# outputs-voltage-and-current-measurements.net
KiCad netlist of a schematic drawn in Altium Designer
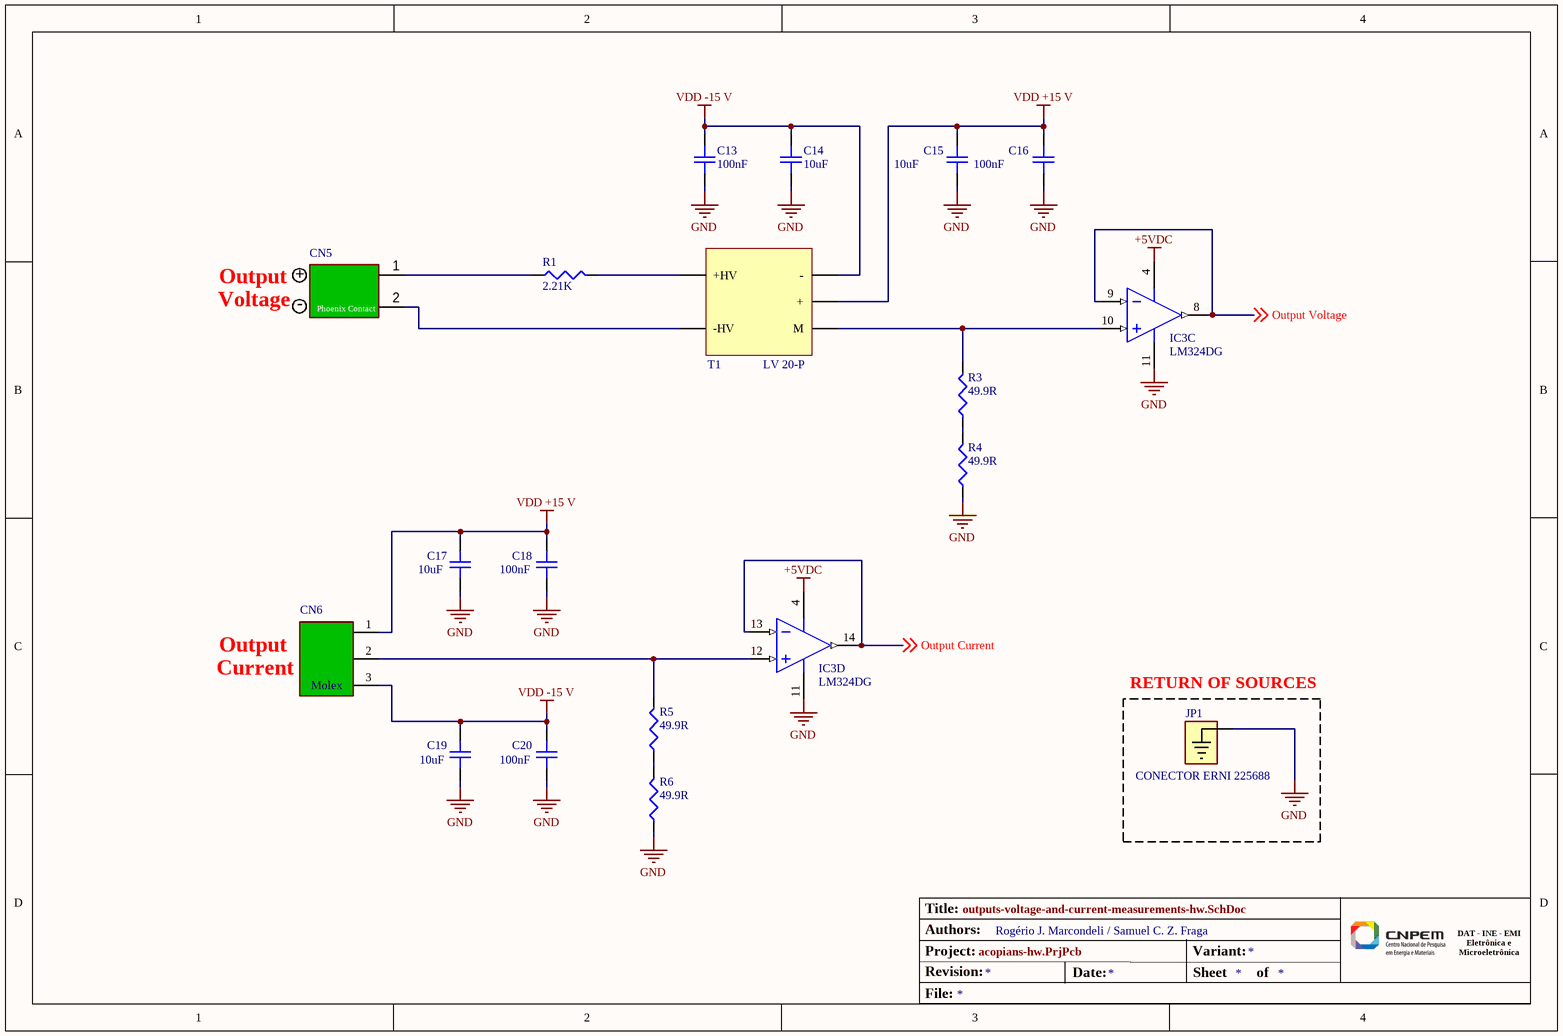
[diagram p0: outputs-voltage-and-current-measurements-hw.SchDoc]

(export (version "E")
  (design (tool "Eeschema 10.0.6"))
  (components
    (comp (ref "C13")
      (value "100nF")
      (footprint "C0805")
      (description "Capacitor 0.1UF 50V X7R 0805")
      (fields (field (name "TOLERANCE") "10%") (field (name "VOLTAGE") "50V"))
      (libsource (lib "acopians-monitoring-hw-library-schematic") (part "CAPACITOR 100nF/50V"))
    )
    (comp (ref "C14")
      (value "10uF")
      (footprint "C0805")
      (description "Capacitor 10UF 35V X5R 0805")
      (fields
        (field (name "MANUFACTURER") "TDK")
        (field (name "MANUFACTURER PART NUMBER") "C2012X5R1V106K085AC")
      )
      (libsource (lib "acopians-monitoring-hw-library-schematic") (part "CAPACITOR 10uF/35V"))
    )
    (comp (ref "C15")
      (value "10uF")
      (footprint "C0805")
      (description "Capacitor 10UF 35V X5R 0805")
      (fields
        (field (name "MANUFACTURER") "TDK")
        (field (name "MANUFACTURER PART NUMBER") "C2012X5R1V106K085AC")
      )
      (libsource (lib "acopians-monitoring-hw-library-schematic") (part "CAPACITOR 10uF/35V"))
    )
    (comp (ref "C16")
      (value "100nF")
      (footprint "C0805")
      (description "Capacitor 0.1UF 50V X7R 0805")
      (fields (field (name "TOLERANCE") "10%") (field (name "VOLTAGE") "50V"))
      (libsource (lib "acopians-monitoring-hw-library-schematic") (part "CAPACITOR 100nF/50V"))
    )
    (comp (ref "C17")
      (value "10uF")
      (footprint "C0805")
      (description "Capacitor 10UF 35V X5R 0805")
      (fields
        (field (name "MANUFACTURER") "TDK")
        (field (name "MANUFACTURER PART NUMBER") "C2012X5R1V106K085AC")
      )
      (libsource (lib "acopians-monitoring-hw-library-schematic") (part "CAPACITOR 10uF/35V"))
    )
    (comp (ref "C18")
      (value "100nF")
      (footprint "C0805")
      (description "Capacitor 0.1UF 50V X7R 0805")
      (fields (field (name "TOLERANCE") "10%") (field (name "VOLTAGE") "50V"))
      (libsource (lib "acopians-monitoring-hw-library-schematic") (part "CAPACITOR 100nF/50V"))
    )
    (comp (ref "C19")
      (value "10uF")
      (footprint "C0805")
      (description "Capacitor 10UF 35V X5R 0805")
      (fields
        (field (name "MANUFACTURER") "TDK")
        (field (name "MANUFACTURER PART NUMBER") "C2012X5R1V106K085AC")
      )
      (libsource (lib "acopians-monitoring-hw-library-schematic") (part "CAPACITOR 10uF/35V"))
    )
    (comp (ref "C20")
      (value "100nF")
      (footprint "C0805")
      (description "Capacitor 0.1UF 50V X7R 0805")
      (fields (field (name "TOLERANCE") "10%") (field (name "VOLTAGE") "50V"))
      (libsource (lib "acopians-monitoring-hw-library-schematic") (part "CAPACITOR 100nF/50V"))
    )
    (comp (ref "CN5")
      (value "1755736")
      (footprint "Conector Phoenix 2 vias 1755736")
      (description "Conector Phoenix 2 vias 1755736")
      (fields (field (name "MANUFACTURER") "Phoenix Contact"))
      (libsource (lib "acopians-monitoring-hw-library-schematic") (part "CONECTOR PHOENIX 2 VIAS 1755736"))
    )
    (comp (ref "CN6")
      (value "Header Molex 3 Pin 22-27-2031")
      (footprint "HEADER MOLEX 22 27 2031")
      (fields
        (field (name "MANUFACTURER") "Molex, LLC")
        (field (name "MANUFACTURER PART NUMBER") "0022272031")
      )
      (libsource (lib "acopians-monitoring-hw-library-schematic") (part "HEADER MOLEX 22-27-2031"))
    )
    (comp (ref "IC3")
      (value "LM324DG")
      (footprint "SOIC-14")
      (description "Operational Amplifiers - Op Amps 3-32V Quad 5mV")
      (libsource (lib "acopians-monitoring-hw-library-schematic") (part "LM324DG"))
    )
    (comp (ref "JP1")
      (value "CONECTOR ERNI 225688")
      (footprint "CONECTOR ERNI 225688")
      (description "Conector ERNI 225688")
      (libsource (lib "acopians-monitoring-hw-library-schematic") (part "CONECTOR ERNI 225688"))
    )
    (comp (ref "R1")
      (value "2.21K")
      (footprint "R0805")
      (description "Resistor SMD 2.21K OHM 1% 1/8W 0805")
      (fields (field (name "TOLERANCE") "0.1%"))
      (libsource (lib "Simulation Generic Components") (part "RESISTOR 1K"))
    )
    (comp (ref "R3")
      (value "49.9R")
      (footprint "R0603")
      (description "Resistor SMD 49.9R OHM 0.1% 1/10W 0603")
      (fields (field (name "TOLERANCE") "0.1%"))
      (libsource (lib "acopians-monitoring-hw-library-schematic") (part "RESISTOR 49.9R"))
    )
    (comp (ref "R4")
      (value "49.9R")
      (footprint "R0603")
      (description "Resistor SMD 49.9R OHM 0.1% 1/10W 0603")
      (fields (field (name "TOLERANCE") "0.1%"))
      (libsource (lib "acopians-monitoring-hw-library-schematic") (part "RESISTOR 49.9R"))
    )
    (comp (ref "R5")
      (value "49.9R")
      (footprint "R0603")
      (description "Resistor SMD 49.9R OHM 0.1% 1/10W 0603")
      (fields (field (name "TOLERANCE") "0.1%"))
      (libsource (lib "acopians-monitoring-hw-library-schematic") (part "RESISTOR 49.9R"))
    )
    (comp (ref "R6")
      (value "49.9R")
      (footprint "R0603")
      (description "Resistor SMD 49.9R OHM 0.1% 1/10W 0603")
      (fields (field (name "TOLERANCE") "0.1%"))
      (libsource (lib "acopians-monitoring-hw-library-schematic") (part "RESISTOR 49.9R"))
    )
    (comp (ref "T1")
      (value "Voltagem Transducer LV 20-P")
      (footprint "VOLTAGE TRANSDUCER LV 20-P")
      (fields
        (field (name "MANUFACTURER") "LEM USA Inc.")
        (field (name "MANUFACTURER PART NUMBER") "LV 20-P")
        (field (name "TEXT") "LV 20-P")
      )
      (libsource (lib "acopians-monitoring-hw-library-schematic") (part "VOLTAGE TRANSDUCER LV 20-P"))
    )
  )
  (nets
    (net (code "1") (name "+5VDC") (class "Default")
      (node (ref "IC3") (pin "4") (pinfunction "V+_4") (pintype "power_in"))
    )
    (net (code "2") (name "GND") (class "Default")
      (node (ref "C13") (pin "1") (pinfunction "1_1") (pintype "passive"))
      (node (ref "C14") (pin "1") (pinfunction "1_1") (pintype "passive"))
      (node (ref "C15") (pin "1") (pinfunction "1_1") (pintype "passive"))
      (node (ref "C16") (pin "1") (pinfunction "1_1") (pintype "passive"))
      (node (ref "C17") (pin "1") (pinfunction "1_1") (pintype "passive"))
      (node (ref "C18") (pin "1") (pinfunction "1_1") (pintype "passive"))
      (node (ref "C19") (pin "1") (pinfunction "1_1") (pintype "passive"))
      (node (ref "C20") (pin "1") (pinfunction "1_1") (pintype "passive"))
      (node (ref "IC3") (pin "11") (pinfunction "V-_11") (pintype "power_in"))
      (node (ref "JP1") (pin "1") (pinfunction "1_1") (pintype "passive"))
      (node (ref "R4") (pin "1") (pinfunction "1_1") (pintype "passive"))
      (node (ref "R6") (pin "1") (pinfunction "1_1") (pintype "passive"))
    )
    (net (code "3") (name "Net-(CN5-Pad1)") (class "Default")
      (node (ref "CN5") (pin "1") (pinfunction "1_1") (pintype "passive"))
      (node (ref "R1") (pin "1") (pinfunction "1_1") (pintype "passive"))
    )
    (net (code "4") (name "Net-(CN6-M)") (class "Default")
      (node (ref "CN6") (pin "2") (pinfunction "M_2") (pintype "passive"))
      (node (ref "IC3") (pin "12") (pinfunction "IN_D+_12") (pintype "input"))
      (node (ref "R5") (pin "2") (pinfunction "2_2") (pintype "passive"))
    )
    (net (code "5") (name "Net-(IC3C-IN_C+)") (class "Default")
      (node (ref "IC3") (pin "10") (pinfunction "IN_C+_10") (pintype "input"))
      (node (ref "R3") (pin "2") (pinfunction "2_2") (pintype "passive"))
      (node (ref "T1") (pin "5") (pinfunction "M_5") (pintype "passive"))
    )
    (net (code "6") (name "Net-(R3-Pad1)") (class "Default")
      (node (ref "R3") (pin "1") (pinfunction "1_1") (pintype "passive"))
      (node (ref "R4") (pin "2") (pinfunction "2_2") (pintype "passive"))
    )
    (net (code "7") (name "Net-(R5-Pad1)") (class "Default")
      (node (ref "R5") (pin "1") (pinfunction "1_1") (pintype "passive"))
      (node (ref "R6") (pin "2") (pinfunction "2_2") (pintype "passive"))
    )
    (net (code "8") (name "Net-(T1-+HV)") (class "Default")
      (node (ref "R1") (pin "2") (pinfunction "2_2") (pintype "passive"))
      (node (ref "T1") (pin "1") (pinfunction "+HV_1") (pintype "passive"))
    )
    (net (code "9") (name "Net-(T1--HV)") (class "Default")
      (node (ref "CN5") (pin "2") (pinfunction "2_2") (pintype "passive"))
      (node (ref "T1") (pin "2") (pinfunction "-HV_2") (pintype "passive"))
    )
    (net (code "10") (name "Output Current") (class "Default")
      (node (ref "IC3") (pin "13") (pinfunction "IN_D-_13") (pintype "input"))
      (node (ref "IC3") (pin "14") (pinfunction "OUT_D_14") (pintype "output"))
    )
    (net (code "11") (name "Output Voltage") (class "Default")
      (node (ref "IC3") (pin "8") (pinfunction "OUT_C_8") (pintype "output"))
      (node (ref "IC3") (pin "9") (pinfunction "IN_C-_9") (pintype "input"))
    )
    (net (code "12") (name "VDD +15 V") (class "Default")
      (node (ref "C15") (pin "2") (pinfunction "2_2") (pintype "passive"))
      (node (ref "C16") (pin "2") (pinfunction "2_2") (pintype "passive"))
      (node (ref "C17") (pin "2") (pinfunction "2_2") (pintype "passive"))
      (node (ref "C18") (pin "2") (pinfunction "2_2") (pintype "passive"))
      (node (ref "CN6") (pin "1") (pinfunction "+15V_1") (pintype "passive"))
      (node (ref "T1") (pin "4") (pinfunction "+_4") (pintype "passive"))
    )
    (net (code "13") (name "VDD -15 V") (class "Default")
      (node (ref "C13") (pin "2") (pinfunction "2_2") (pintype "passive"))
      (node (ref "C14") (pin "2") (pinfunction "2_2") (pintype "passive"))
      (node (ref "C19") (pin "2") (pinfunction "2_2") (pintype "passive"))
      (node (ref "C20") (pin "2") (pinfunction "2_2") (pintype "passive"))
      (node (ref "CN6") (pin "3") (pinfunction "-15V_3") (pintype "passive"))
      (node (ref "T1") (pin "3") (pinfunction "-_3") (pintype "passive"))
    )
  )
)
